# 6Ch_24Bit_FB_FeatherWing.net
KiCad netlist of a schematic drawn in EAGLE
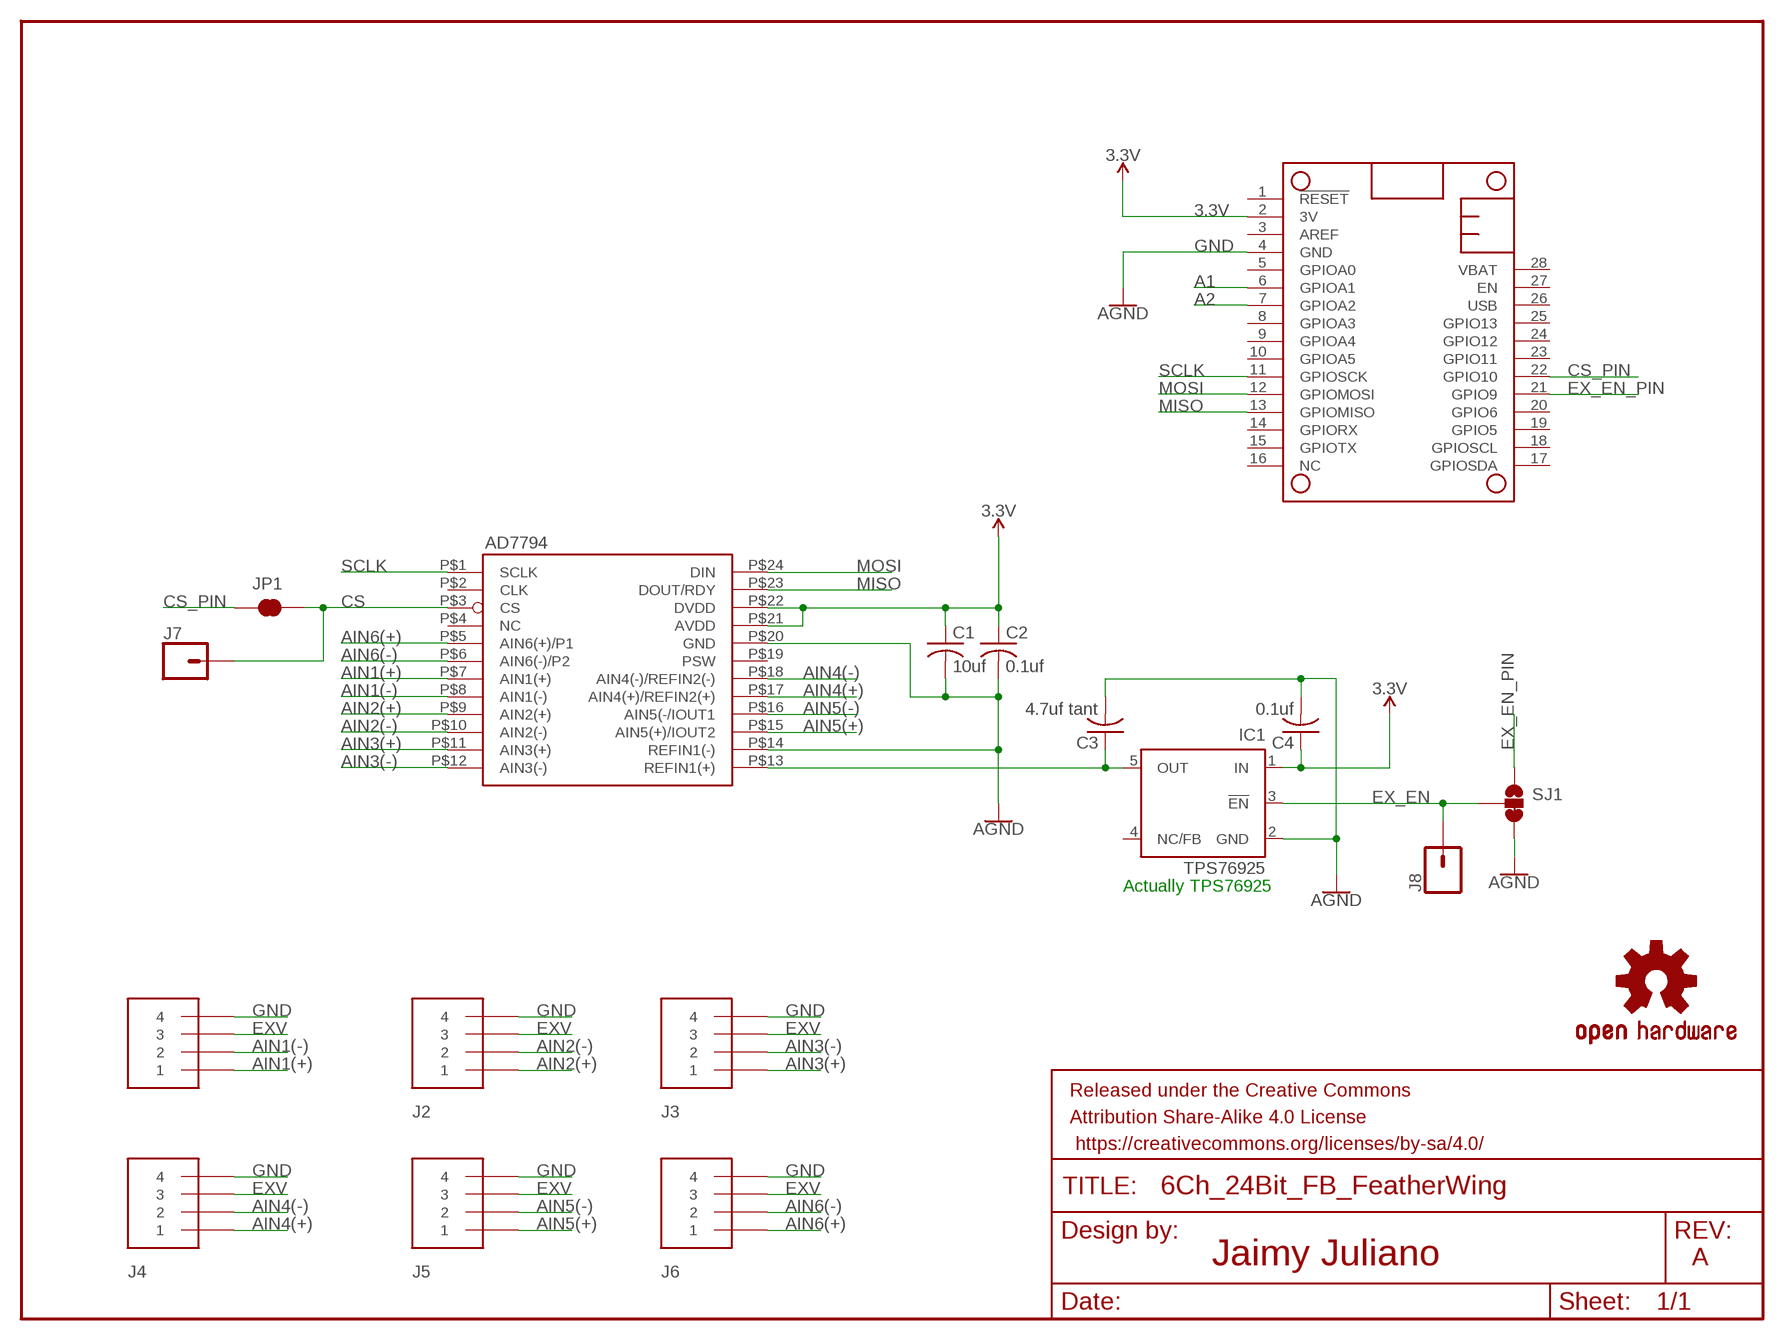
[diagram p0: schematic, sheet 1]

(export (version "E")
  (design (tool "Eeschema 10.0.6"))
  (components
    (comp (ref "C1")
      (value "10uf")
      (footprint "eagle-import:C0603")
      (libsource (lib "eagle-import") (part "C-USC0603"))
    )
    (comp (ref "C2")
      (value "0.1uf")
      (footprint "eagle-import:C0603")
      (libsource (lib "eagle-import") (part "C-USC0603"))
    )
    (comp (ref "C3")
      (value "4.7uf tant")
      (footprint "eagle-import:C1206K")
      (libsource (lib "eagle-import") (part "C-USC1206K"))
    )
    (comp (ref "C4")
      (value "0.1uf")
      (footprint "eagle-import:C0603")
      (libsource (lib "eagle-import") (part "C-USC0603"))
    )
    (comp (ref "FRAME2")
      (value "FRAME-LETTER")
      (footprint "eagle-import:CREATIVE_COMMONS")
      (libsource (lib "eagle-import") (part "FRAME-LETTER"))
    )
    (comp (ref "IC1")
      (value "TPS76925")
      (footprint "eagle-import:SOT23-DBV")
      (libsource (lib "eagle-import") (part "TPS77025"))
    )
    (comp (ref "J1")
      (value "CON_PTSM_SOCKET-4-PTH-VERT")
      (footprint "eagle-import:CON_PTSM_SOCKET-4-PTH-VERT")
      (libsource (lib "eagle-import") (part "CON_PTSM_SOCKET-4-PTH-VERT"))
    )
    (comp (ref "J2")
      (value "CON_PTSM_SOCKET-4-PTH-VERT")
      (footprint "eagle-import:CON_PTSM_SOCKET-4-PTH-VERT")
      (libsource (lib "eagle-import") (part "CON_PTSM_SOCKET-4-PTH-VERT"))
    )
    (comp (ref "J3")
      (value "CON_PTSM_SOCKET-4-PTH-VERT")
      (footprint "eagle-import:CON_PTSM_SOCKET-4-PTH-VERT")
      (libsource (lib "eagle-import") (part "CON_PTSM_SOCKET-4-PTH-VERT"))
    )
    (comp (ref "J4")
      (value "CON_PTSM_SOCKET-4-PTH-VERT")
      (footprint "eagle-import:CON_PTSM_SOCKET-4-PTH-VERT")
      (libsource (lib "eagle-import") (part "CON_PTSM_SOCKET-4-PTH-VERT"))
    )
    (comp (ref "J5")
      (value "CON_PTSM_SOCKET-4-PTH-VERT")
      (footprint "eagle-import:CON_PTSM_SOCKET-4-PTH-VERT")
      (libsource (lib "eagle-import") (part "CON_PTSM_SOCKET-4-PTH-VERT"))
    )
    (comp (ref "J6")
      (value "CON_PTSM_SOCKET-4-PTH-VERT")
      (footprint "eagle-import:CON_PTSM_SOCKET-4-PTH-VERT")
      (libsource (lib "eagle-import") (part "CON_PTSM_SOCKET-4-PTH-VERT"))
    )
    (comp (ref "J7")
      (value "CONN_01PTH_NO_SILK_YES_STOP")
      (footprint "eagle-import:1X01_NO_SILK")
      (libsource (lib "eagle-import") (part "CONN_01PTH_NO_SILK_YES_STOP"))
    )
    (comp (ref "J8")
      (value "CONN_01PTH_NO_SILK_YES_STOP")
      (footprint "eagle-import:1X01_NO_SILK")
      (libsource (lib "eagle-import") (part "CONN_01PTH_NO_SILK_YES_STOP"))
    )
    (comp (ref "JP1")
      (value "JUMPER-SMT_2_NC_TRACE_NO-SILK")
      (footprint "eagle-import:SMT-JUMPER_2_NC_TRACE_NO-SILK")
      (libsource (lib "eagle-import") (part "JUMPER-SMT_2_NC_TRACE_NO-SILK"))
    )
    (comp (ref "LOGO1")
      (value "OSHW-LOGOS")
      (footprint "eagle-import:OSHW-LOGO-S")
      (libsource (lib "eagle-import") (part "OSHW-LOGOS"))
    )
    (comp (ref "MS1")
      (value "FEATHERWING_NODIM")
      (footprint "eagle-import:FEATHERWING_DIM")
      (libsource (lib "eagle-import") (part "FEATHERWING_NODIM"))
    )
    (comp (ref "SJ1")
      (value "JUMPER-SMT_3_1-NC_TRACE_NO-SILK")
      (footprint "eagle-import:SMT-JUMPER_3_1-NC_TRACE_NO-SILK")
      (libsource (lib "eagle-import") (part "JUMPER-SMT_3_1-NC_TRACE_NO-SILK"))
    )
    (comp (ref "U1")
      (value "AD7794")
      (footprint "eagle-import:TSSOP-24")
      (libsource (lib "eagle-import") (part "AD7794"))
    )
  )
  (nets
    (net (code "1") (name "/A1") (class "Default")
      (node (ref "MS1") (pin "6") (pinfunction "GPIOA1_6") (pintype "bidirectional"))
    )
    (net (code "2") (name "/A2") (class "Default")
      (node (ref "MS1") (pin "7") (pinfunction "GPIOA2_7") (pintype "bidirectional"))
    )
    (net (code "3") (name "/AIN1(+)") (class "Default")
      (node (ref "J1") (pin "P$1") (pinfunction "1_P$1") (pintype "bidirectional"))
      (node (ref "U1") (pin "P$7") (pinfunction "AIN1(+)_P$7") (pintype "bidirectional"))
    )
    (net (code "4") (name "/AIN1(-)") (class "Default")
      (node (ref "J1") (pin "P$2") (pinfunction "2_P$2") (pintype "bidirectional"))
      (node (ref "U1") (pin "P$8") (pinfunction "AIN1(-)_P$8") (pintype "bidirectional"))
    )
    (net (code "5") (name "/AIN2(+)") (class "Default")
      (node (ref "J2") (pin "P$1") (pinfunction "1_P$1") (pintype "bidirectional"))
      (node (ref "U1") (pin "P$9") (pinfunction "AIN2(+)_P$9") (pintype "bidirectional"))
    )
    (net (code "6") (name "/AIN2(-)") (class "Default")
      (node (ref "J2") (pin "P$2") (pinfunction "2_P$2") (pintype "bidirectional"))
      (node (ref "U1") (pin "P$10") (pinfunction "AIN2(-)_P$10") (pintype "bidirectional"))
    )
    (net (code "7") (name "/AIN3(+)") (class "Default")
      (node (ref "J3") (pin "P$1") (pinfunction "1_P$1") (pintype "bidirectional"))
      (node (ref "U1") (pin "P$11") (pinfunction "AIN3(+)_P$11") (pintype "bidirectional"))
    )
    (net (code "8") (name "/AIN3(-)") (class "Default")
      (node (ref "J3") (pin "P$2") (pinfunction "2_P$2") (pintype "bidirectional"))
      (node (ref "U1") (pin "P$12") (pinfunction "AIN3(-)_P$12") (pintype "bidirectional"))
    )
    (net (code "9") (name "/AIN4(+)") (class "Default")
      (node (ref "J4") (pin "P$1") (pinfunction "1_P$1") (pintype "bidirectional"))
      (node (ref "U1") (pin "P$17") (pinfunction "AIN4(+)/REFIN2(+)_P$17") (pintype "bidirectional"))
    )
    (net (code "10") (name "/AIN4(-)") (class "Default")
      (node (ref "J4") (pin "P$2") (pinfunction "2_P$2") (pintype "bidirectional"))
      (node (ref "U1") (pin "P$18") (pinfunction "AIN4(-)/REFIN2(-)_P$18") (pintype "bidirectional"))
    )
    (net (code "11") (name "/AIN5(+)") (class "Default")
      (node (ref "J5") (pin "P$1") (pinfunction "1_P$1") (pintype "bidirectional"))
      (node (ref "U1") (pin "P$15") (pinfunction "AIN5(+)/IOUT2_P$15") (pintype "bidirectional"))
    )
    (net (code "12") (name "/AIN5(-)") (class "Default")
      (node (ref "J5") (pin "P$2") (pinfunction "2_P$2") (pintype "bidirectional"))
      (node (ref "U1") (pin "P$16") (pinfunction "AIN5(-/IOUT1_P$16") (pintype "bidirectional"))
    )
    (net (code "13") (name "/AIN6(+)") (class "Default")
      (node (ref "J6") (pin "P$1") (pinfunction "1_P$1") (pintype "bidirectional"))
      (node (ref "U1") (pin "P$5") (pinfunction "AIN6(+)/P1_P$5") (pintype "bidirectional"))
    )
    (net (code "14") (name "/AIN6(-)") (class "Default")
      (node (ref "J6") (pin "P$2") (pinfunction "2_P$2") (pintype "bidirectional"))
      (node (ref "U1") (pin "P$6") (pinfunction "AIN6(-)/P2_P$6") (pintype "bidirectional"))
    )
    (net (code "15") (name "/CS") (class "Default")
      (node (ref "J7") (pin "1") (pinfunction "1_1") (pintype "passive"))
      (node (ref "JP1") (pin "2") (pinfunction "2_2") (pintype "passive"))
      (node (ref "U1") (pin "P$3") (pinfunction "CS_P$3") (pintype "bidirectional"))
    )
    (net (code "16") (name "/CS_PIN") (class "Default")
      (node (ref "JP1") (pin "1") (pinfunction "1_1") (pintype "passive"))
      (node (ref "MS1") (pin "22") (pinfunction "GPIO10_22") (pintype "bidirectional"))
    )
    (net (code "17") (name "/EXV") (class "Default")
      (node (ref "C3") (pin "1") (pinfunction "1_1") (pintype "passive"))
      (node (ref "IC1") (pin "5") (pinfunction "OUT_5") (pintype "passive"))
      (node (ref "J1") (pin "P$3") (pinfunction "3_P$3") (pintype "bidirectional"))
      (node (ref "J2") (pin "P$3") (pinfunction "3_P$3") (pintype "bidirectional"))
      (node (ref "J3") (pin "P$3") (pinfunction "3_P$3") (pintype "bidirectional"))
      (node (ref "J4") (pin "P$3") (pinfunction "3_P$3") (pintype "bidirectional"))
      (node (ref "J5") (pin "P$3") (pinfunction "3_P$3") (pintype "bidirectional"))
      (node (ref "J6") (pin "P$3") (pinfunction "3_P$3") (pintype "bidirectional"))
      (node (ref "U1") (pin "P$13") (pinfunction "REFIN1(+)_P$13") (pintype "bidirectional"))
    )
    (net (code "18") (name "/EX_EN") (class "Default")
      (node (ref "IC1") (pin "3") (pinfunction "~{EN}_3") (pintype "input"))
      (node (ref "J8") (pin "1") (pinfunction "1_1") (pintype "passive"))
      (node (ref "SJ1") (pin "2") (pinfunction "2_2") (pintype "passive"))
    )
    (net (code "19") (name "/EX_EN_PIN") (class "Default")
      (node (ref "MS1") (pin "21") (pinfunction "GPIO9_21") (pintype "bidirectional"))
      (node (ref "SJ1") (pin "1") (pinfunction "1_1") (pintype "passive"))
    )
    (net (code "20") (name "/MISO") (class "Default")
      (node (ref "MS1") (pin "13") (pinfunction "GPIOMISO_13") (pintype "bidirectional"))
      (node (ref "U1") (pin "P$23") (pinfunction "DOUT/RDY_P$23") (pintype "bidirectional"))
    )
    (net (code "21") (name "/MOSI") (class "Default")
      (node (ref "MS1") (pin "12") (pinfunction "GPIOMOSI_12") (pintype "bidirectional"))
      (node (ref "U1") (pin "P$24") (pinfunction "DIN_P$24") (pintype "bidirectional"))
    )
    (net (code "22") (name "/SCLK") (class "Default")
      (node (ref "MS1") (pin "11") (pinfunction "GPIOSCK_11") (pintype "bidirectional"))
      (node (ref "U1") (pin "P$1") (pinfunction "SCLK_P$1") (pintype "bidirectional"))
    )
    (net (code "23") (name "/USB") (class "Default")
      (node (ref "MS1") (pin "26") (pinfunction "USB_26") (pintype "power_in"))
    )
    (net (code "24") (name "/VBAT") (class "Default")
      (node (ref "MS1") (pin "28") (pinfunction "VBAT_28") (pintype "power_in"))
    )
    (net (code "25") (name "3.3V") (class "Default")
      (node (ref "C1") (pin "1") (pinfunction "1_1") (pintype "passive"))
      (node (ref "C2") (pin "1") (pinfunction "1_1") (pintype "passive"))
      (node (ref "C4") (pin "1") (pinfunction "1_1") (pintype "passive"))
      (node (ref "IC1") (pin "1") (pinfunction "IN_1") (pintype "input"))
      (node (ref "MS1") (pin "2") (pinfunction "3V_2") (pintype "power_in"))
      (node (ref "U1") (pin "P$21") (pinfunction "AVDD_P$21") (pintype "bidirectional"))
      (node (ref "U1") (pin "P$22") (pinfunction "DVDD_P$22") (pintype "bidirectional"))
    )
    (net (code "26") (name "AGND") (class "Default")
      (node (ref "C1") (pin "2") (pinfunction "2_2") (pintype "passive"))
      (node (ref "C2") (pin "2") (pinfunction "2_2") (pintype "passive"))
      (node (ref "C3") (pin "2") (pinfunction "2_2") (pintype "passive"))
      (node (ref "C4") (pin "2") (pinfunction "2_2") (pintype "passive"))
      (node (ref "IC1") (pin "2") (pinfunction "GND_2") (pintype "power_in"))
      (node (ref "J1") (pin "P$4") (pinfunction "4_P$4") (pintype "bidirectional"))
      (node (ref "J2") (pin "P$4") (pinfunction "4_P$4") (pintype "bidirectional"))
      (node (ref "J3") (pin "P$4") (pinfunction "4_P$4") (pintype "bidirectional"))
      (node (ref "J4") (pin "P$4") (pinfunction "4_P$4") (pintype "bidirectional"))
      (node (ref "J5") (pin "P$4") (pinfunction "4_P$4") (pintype "bidirectional"))
      (node (ref "J6") (pin "P$4") (pinfunction "4_P$4") (pintype "bidirectional"))
      (node (ref "MS1") (pin "4") (pinfunction "GND_4") (pintype "power_in"))
      (node (ref "SJ1") (pin "3") (pinfunction "3_3") (pintype "passive"))
      (node (ref "U1") (pin "P$14") (pinfunction "REFIN1(-)_P$14") (pintype "bidirectional"))
      (node (ref "U1") (pin "P$20") (pinfunction "GND_P$20") (pintype "bidirectional"))
    )
    (net (code "27") (name "unconnected-(IC1-NC{slash}FB-Pad4)") (class "Default")
      (node (ref "IC1") (pin "4") (pinfunction "NC/FB_4") (pintype "passive"))
    )
    (net (code "28") (name "unconnected-(MS1-AREF-Pad3)") (class "Default")
      (node (ref "MS1") (pin "3") (pinfunction "AREF_3") (pintype "passive"))
    )
    (net (code "29") (name "unconnected-(MS1-EN-Pad27)") (class "Default")
      (node (ref "MS1") (pin "27") (pinfunction "EN_27") (pintype "passive"))
    )
    (net (code "30") (name "unconnected-(MS1-GPIO5-Pad19)") (class "Default")
      (node (ref "MS1") (pin "19") (pinfunction "GPIO5_19") (pintype "bidirectional"))
    )
    (net (code "31") (name "unconnected-(MS1-GPIO6-Pad20)") (class "Default")
      (node (ref "MS1") (pin "20") (pinfunction "GPIO6_20") (pintype "bidirectional"))
    )
    (net (code "32") (name "unconnected-(MS1-GPIO11-Pad23)") (class "Default")
      (node (ref "MS1") (pin "23") (pinfunction "GPIO11_23") (pintype "bidirectional"))
    )
    (net (code "33") (name "unconnected-(MS1-GPIO12-Pad24)") (class "Default")
      (node (ref "MS1") (pin "24") (pinfunction "GPIO12_24") (pintype "bidirectional"))
    )
    (net (code "34") (name "unconnected-(MS1-GPIO13-Pad25)") (class "Default")
      (node (ref "MS1") (pin "25") (pinfunction "GPIO13_25") (pintype "bidirectional"))
    )
    (net (code "35") (name "unconnected-(MS1-GPIOA0-Pad5)") (class "Default")
      (node (ref "MS1") (pin "5") (pinfunction "GPIOA0_5") (pintype "bidirectional"))
    )
    (net (code "36") (name "unconnected-(MS1-GPIOA3-Pad8)") (class "Default")
      (node (ref "MS1") (pin "8") (pinfunction "GPIOA3_8") (pintype "bidirectional"))
    )
    (net (code "37") (name "unconnected-(MS1-GPIOA4-Pad9)") (class "Default")
      (node (ref "MS1") (pin "9") (pinfunction "GPIOA4_9") (pintype "bidirectional"))
    )
    (net (code "38") (name "unconnected-(MS1-GPIOA5-Pad10)") (class "Default")
      (node (ref "MS1") (pin "10") (pinfunction "GPIOA5_10") (pintype "bidirectional"))
    )
    (net (code "39") (name "unconnected-(MS1-GPIORX-Pad14)") (class "Default")
      (node (ref "MS1") (pin "14") (pinfunction "GPIORX_14") (pintype "bidirectional"))
    )
    (net (code "40") (name "unconnected-(MS1-GPIOSCL-Pad18)") (class "Default")
      (node (ref "MS1") (pin "18") (pinfunction "GPIOSCL_18") (pintype "bidirectional"))
    )
    (net (code "41") (name "unconnected-(MS1-GPIOSDA-Pad17)") (class "Default")
      (node (ref "MS1") (pin "17") (pinfunction "GPIOSDA_17") (pintype "bidirectional"))
    )
    (net (code "42") (name "unconnected-(MS1-GPIOTX-Pad15)") (class "Default")
      (node (ref "MS1") (pin "15") (pinfunction "GPIOTX_15") (pintype "bidirectional"))
    )
    (net (code "43") (name "unconnected-(MS1-NC-Pad16)") (class "Default")
      (node (ref "MS1") (pin "16") (pinfunction "NC_16") (pintype "passive"))
    )
    (net (code "44") (name "unconnected-(MS1-~{RESET}-Pad1)") (class "Default")
      (node (ref "MS1") (pin "1") (pinfunction "~{RESET}_1") (pintype "input"))
    )
    (net (code "45") (name "unconnected-(U1-CLK-PadP$2)") (class "Default")
      (node (ref "U1") (pin "P$2") (pinfunction "CLK_P$2") (pintype "bidirectional"))
    )
    (net (code "46") (name "unconnected-(U1-NC-PadP$4)") (class "Default")
      (node (ref "U1") (pin "P$4") (pinfunction "NC_P$4") (pintype "bidirectional"))
    )
    (net (code "47") (name "unconnected-(U1-PSW-PadP$19)") (class "Default")
      (node (ref "U1") (pin "P$19") (pinfunction "PSW_P$19") (pintype "bidirectional"))
    )
  )
)
